# schematic.net
KiCad netlist of a schematic drawn in EasyEDA
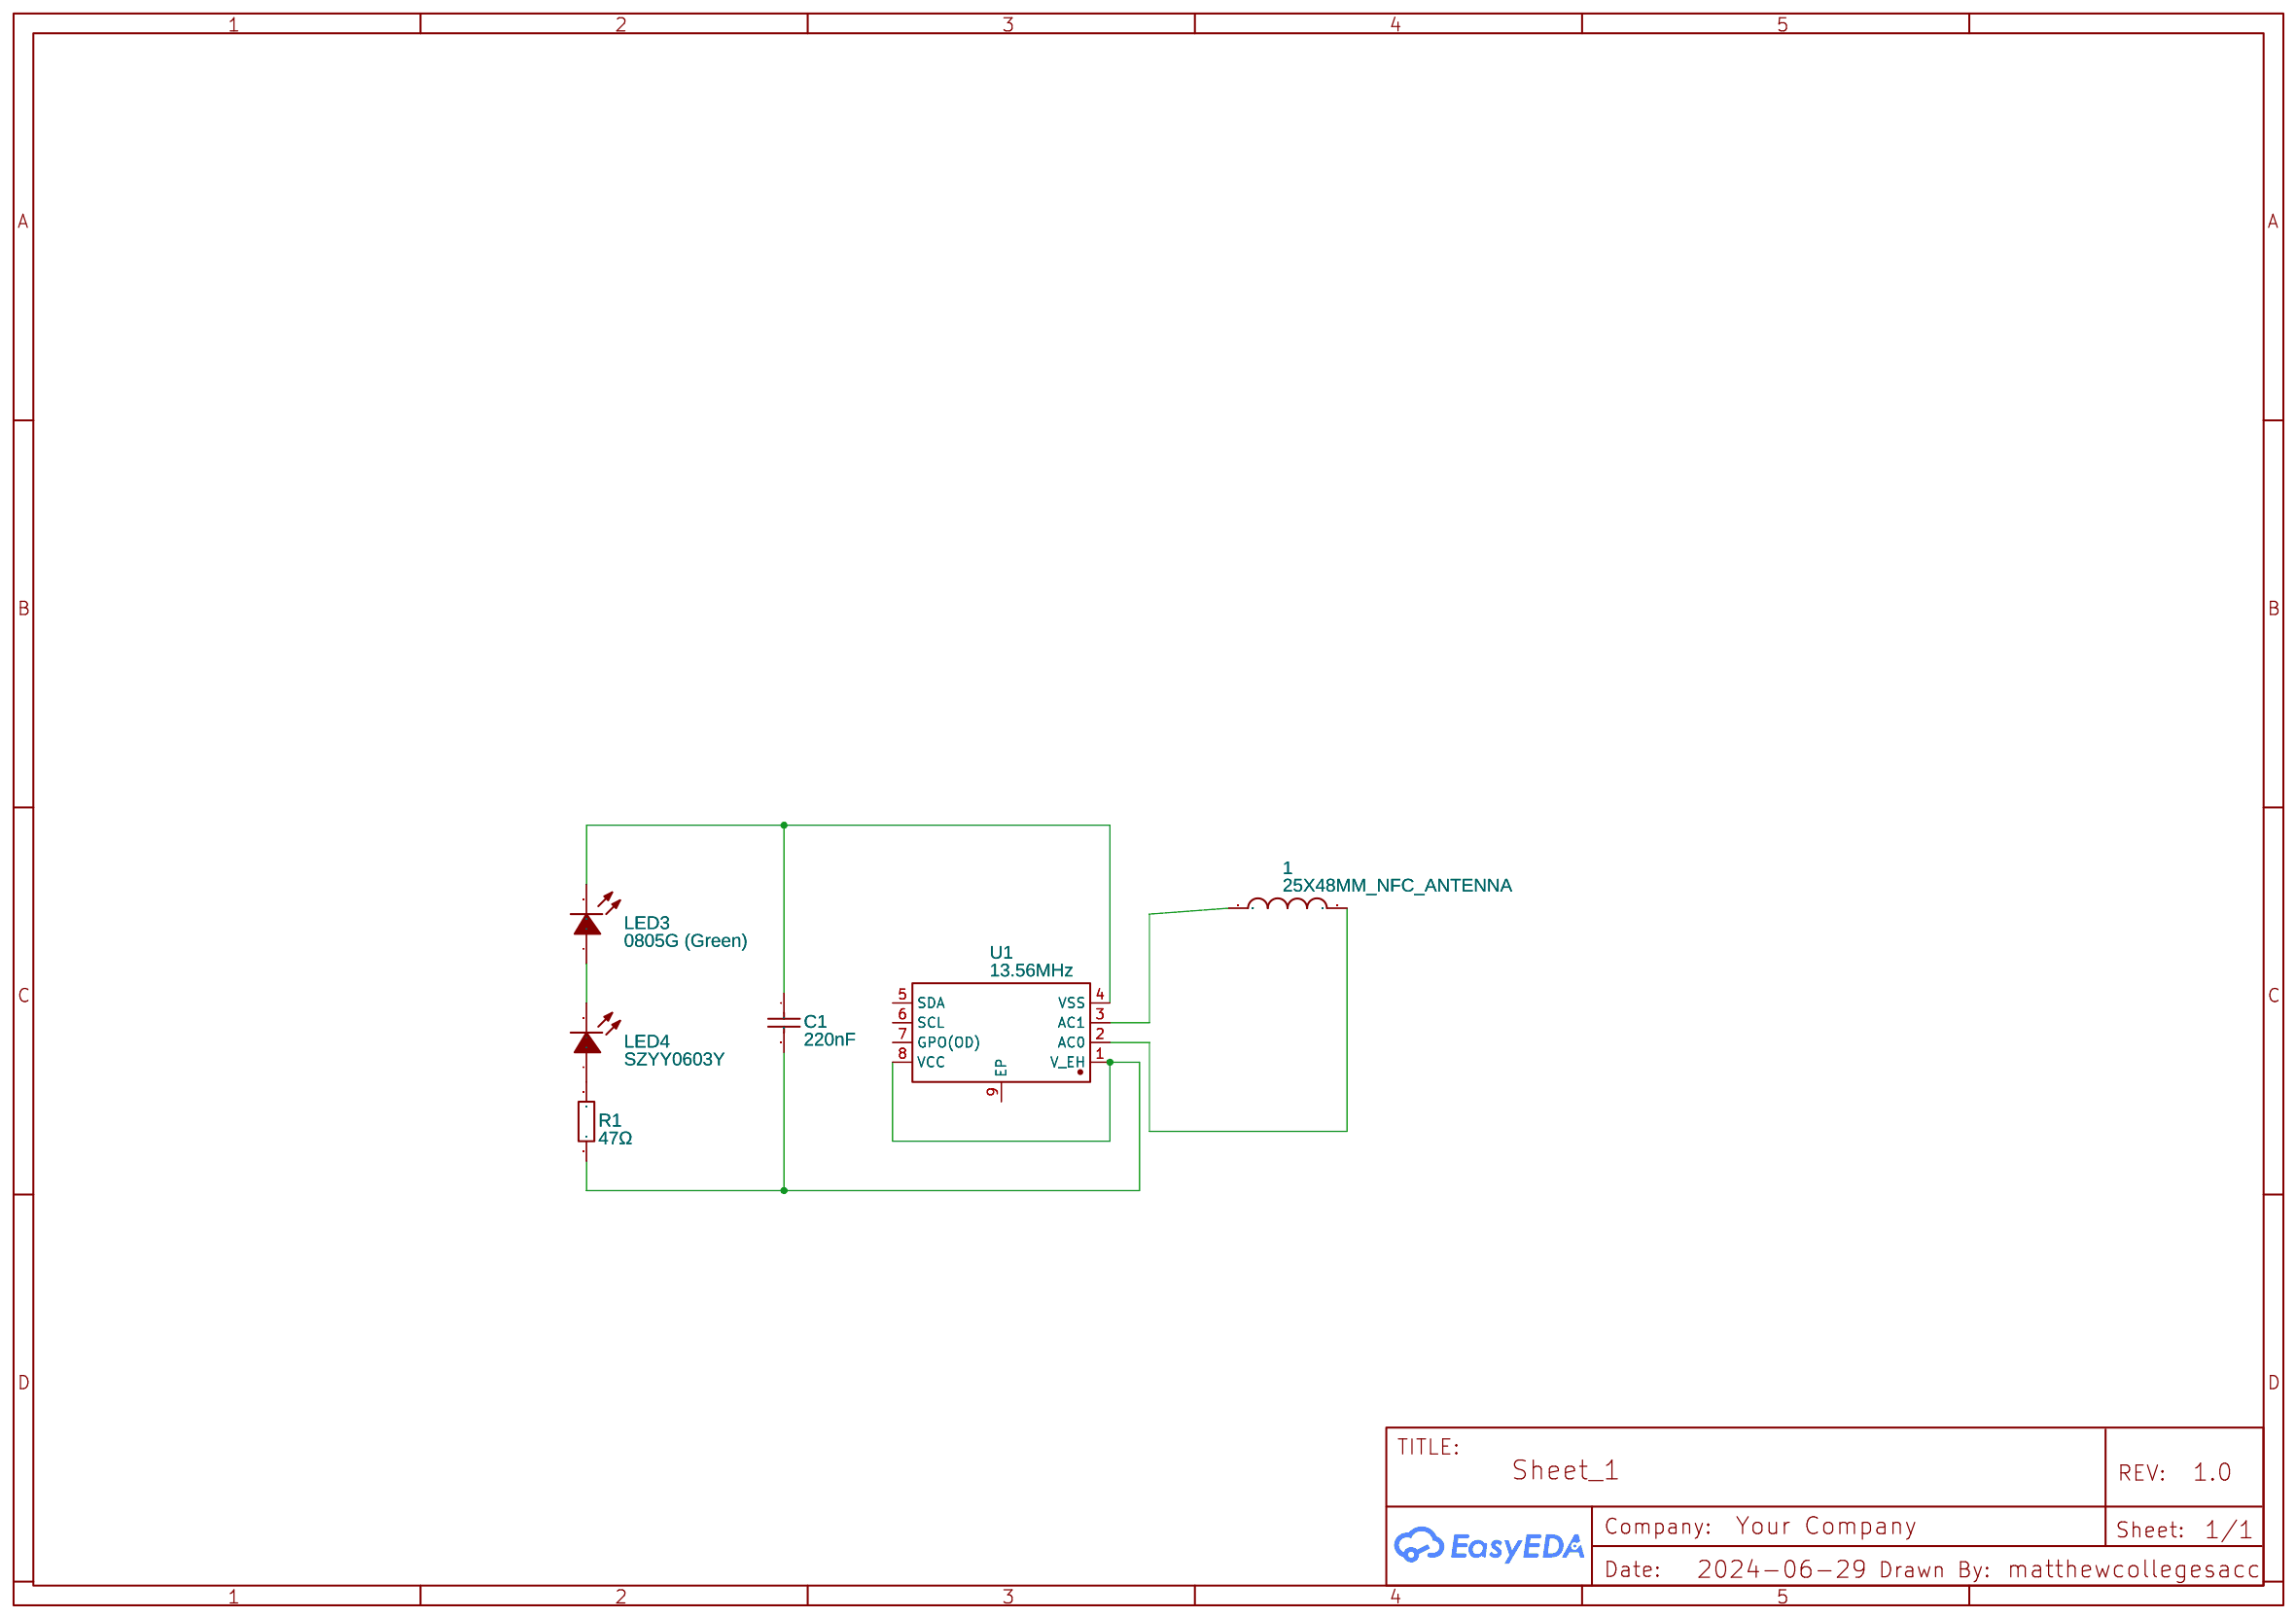
[diagram p0: schematic sheet]

(export (version "E")
  (design (tool "Eeschema 10.0.6"))
  (components
    (comp (ref "1") (value "25X48MM_NFC_ANTENNA") (libsource (lib "") (part "25X48MM_NFC_ANTENNA")))
    (comp (ref "C1")
      (value "220nF")
      (fields
        (field (name "Manufacturer Part") "CL10B224KA8NNNC")
        (field (name "Manufacturer") "SAMSUNG(三星)")
      )
      (libsource (lib "") (part "CL10B224KA8NNNC"))
    )
    (comp (ref "LED3")
      (value "0805G (Green)")
      (fields (field (name "Manufacturer Part") "KT-0805G") (field (name "Manufacturer") "KENTO"))
      (libsource (lib "") (part "0805G (Green)"))
    )
    (comp (ref "LED4")
      (value "SZYY0603Y")
      (fields (field (name "Manufacturer") "yongyu(永裕光电)"))
      (libsource (lib "") (part "SZYY0603Y"))
    )
    (comp (ref "R1")
      (value "47Ω")
      (fields
        (field (name "Manufacturer Part") "0603WAF470JT5E")
        (field (name "Manufacturer") "UNI-ROYAL(厚声)")
      )
      (libsource (lib "") (part "0603WAF470JT5E"))
    )
    (comp (ref "U1")
      (value "13.56MHz")
      (fields (field (name "Manufacturer Part") "ST25DV04K-IER6C3") (field (name "Manufacturer") "ST(意法半导体)"))
      (libsource (lib "") (part "ST25DV04K-IER6C3"))
    )
  )
  (nets
    (net (code "1") (name "Net-(LED3-A)") (class "Default")
      (node (ref "LED3") (pin "1") (pinfunction "A_1") (pintype "unspecified"))
      (node (ref "LED4") (pin "2") (pinfunction "-_2") (pintype "unspecified"))
    )
    (net (code "2") (name "Net-(LED3-K)") (class "Default")
      (node (ref "C1") (pin "1") (pinfunction "1_1") (pintype "input"))
      (node (ref "LED3") (pin "2") (pinfunction "K_2") (pintype "unspecified"))
      (node (ref "U1") (pin "4") (pinfunction "VSS_4") (pintype "unspecified"))
    )
    (net (code "3") (name "Net-(LED4-+)") (class "Default")
      (node (ref "LED4") (pin "1") (pinfunction "+_1") (pintype "unspecified"))
      (node (ref "R1") (pin "1") (pinfunction "1_1") (pintype "input"))
    )
    (net (code "4") (name "Net-(U1-AC0)") (class "Default")
      (node (ref "1") (pin "P$2") (pinfunction "P$2_P$2") (pintype "bidirectional"))
      (node (ref "U1") (pin "2") (pinfunction "AC0_2") (pintype "unspecified"))
    )
    (net (code "5") (name "Net-(U1-AC1)") (class "Default")
      (node (ref "1") (pin "P$1") (pinfunction "P$1_P$1") (pintype "bidirectional"))
      (node (ref "U1") (pin "3") (pinfunction "AC1_3") (pintype "unspecified"))
    )
    (net (code "6") (name "Net-(U1-VCC)") (class "Default")
      (node (ref "C1") (pin "2") (pinfunction "2_2") (pintype "input"))
      (node (ref "R1") (pin "2") (pinfunction "2_2") (pintype "input"))
      (node (ref "U1") (pin "1") (pinfunction "V_EH_1") (pintype "unspecified"))
      (node (ref "U1") (pin "8") (pinfunction "VCC_8") (pintype "unspecified"))
    )
    (net (code "7") (name "unconnected-(U1-EP-Pad9)") (class "Default")
      (node (ref "U1") (pin "9") (pinfunction "EP_9") (pintype "unspecified"))
    )
    (net (code "8") (name "unconnected-(U1-GPO(OD)-Pad7)") (class "Default")
      (node (ref "U1") (pin "7") (pinfunction "GPO(OD)_7") (pintype "unspecified"))
    )
    (net (code "9") (name "unconnected-(U1-SCL-Pad6)") (class "Default")
      (node (ref "U1") (pin "6") (pinfunction "SCL_6") (pintype "unspecified"))
    )
    (net (code "10") (name "unconnected-(U1-SDA-Pad5)") (class "Default")
      (node (ref "U1") (pin "5") (pinfunction "SDA_5") (pintype "unspecified"))
    )
  )
)
